# bunai3.net
KiCad netlist of a schematic drawn in EAGLE
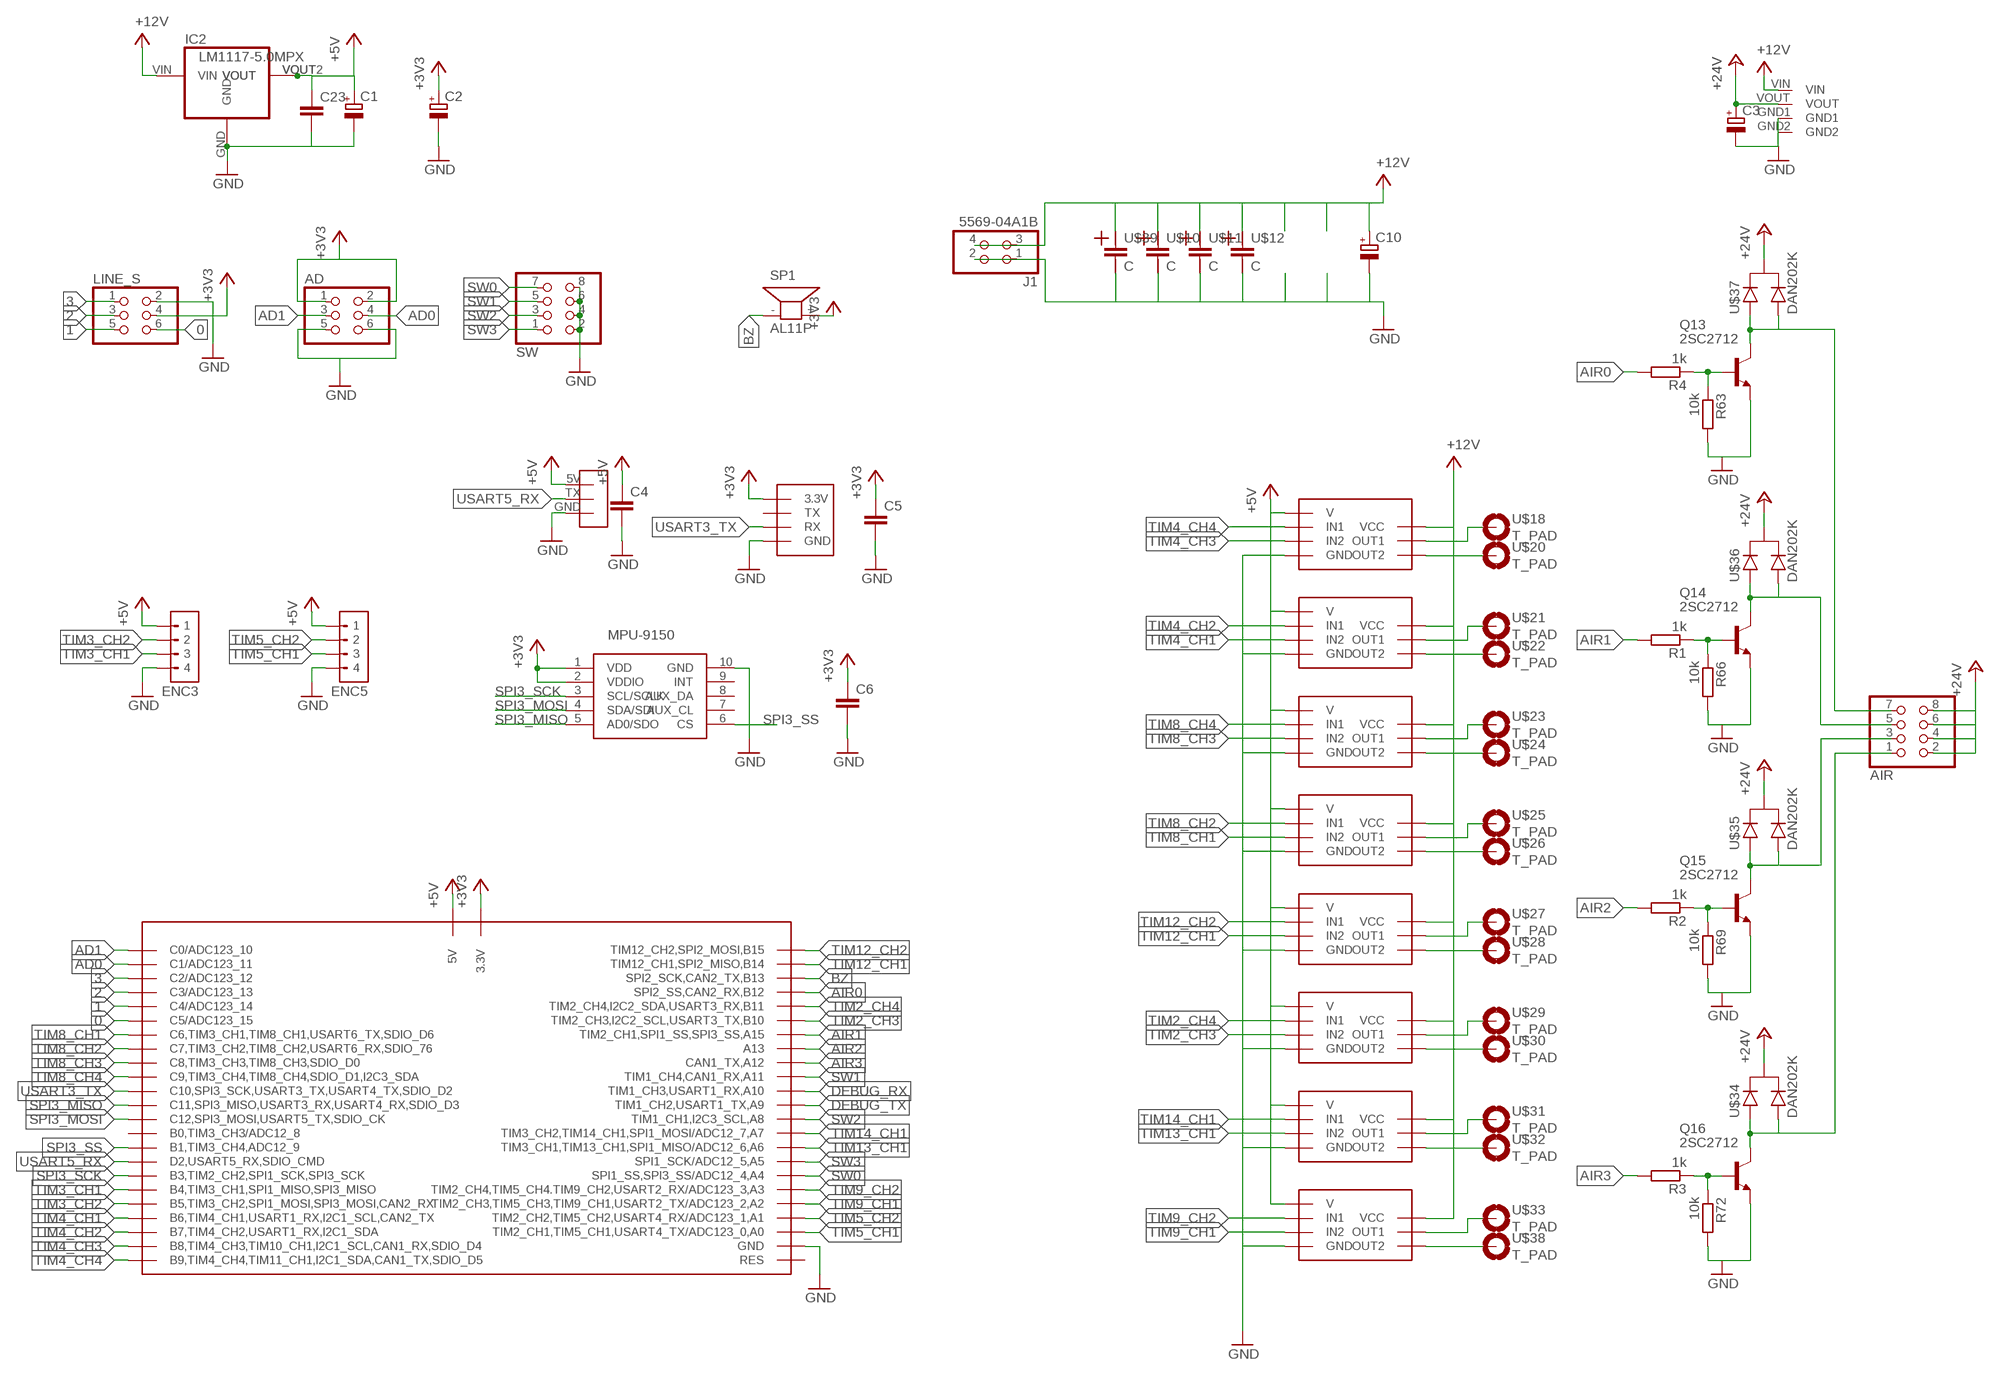
[diagram p0: schematic, sheet 1]

(export (version "E")
  (design (tool "Eeschema 10.0.6"))
  (components
    (comp (ref "AD")
      (value "PINHD-2X3/90")
      (footprint "eagle-import:2X03_90")
      (libsource (lib "eagle-import") (part "PINHD-2X3/90"))
    )
    (comp (ref "AIR")
      (value "PINHD-2X4/90")
      (footprint "eagle-import:2X04_90")
      (libsource (lib "eagle-import") (part "PINHD-2X4/90"))
    )
    (comp (ref "C1")
      (value "CPOL-EUE2.5-6")
      (footprint "eagle-import:E2,5-6")
      (libsource (lib "eagle-import") (part "CPOL-EUE2.5-6"))
    )
    (comp (ref "C2")
      (value "CPOL-EUE2.5-6")
      (footprint "eagle-import:E2,5-6")
      (libsource (lib "eagle-import") (part "CPOL-EUE2.5-6"))
    )
    (comp (ref "C3")
      (value "CPOL-EUE2.5-6")
      (footprint "eagle-import:E2,5-6")
      (libsource (lib "eagle-import") (part "CPOL-EUE2.5-6"))
    )
    (comp (ref "C4")
      (value "C-EU025-024X044")
      (footprint "eagle-import:C025-024X044")
      (libsource (lib "eagle-import") (part "C-EU025-024X044"))
    )
    (comp (ref "C5")
      (value "C-EU025-024X044")
      (footprint "eagle-import:C025-024X044")
      (libsource (lib "eagle-import") (part "C-EU025-024X044"))
    )
    (comp (ref "C6")
      (value "C-EU025-024X044")
      (footprint "eagle-import:C025-024X044")
      (libsource (lib "eagle-import") (part "C-EU025-024X044"))
    )
    (comp (ref "C10")
      (value "CPOL-EUE2.5-6")
      (footprint "eagle-import:E2,5-6")
      (libsource (lib "eagle-import") (part "CPOL-EUE2.5-6"))
    )
    (comp (ref "C23")
      (value "C-EUC0603K")
      (footprint "eagle-import:C0603K")
      (libsource (lib "eagle-import") (part "resistor_C-EUC0603K"))
    )
    (comp (ref "ENC3")
      (value "CN4-JST-XH-TOP")
      (footprint "eagle-import:JST-B4B-XH-A")
      (libsource (lib "eagle-import") (part "CN4-JST-XH-TOP"))
    )
    (comp (ref "ENC5")
      (value "CN4-JST-XH-TOP")
      (footprint "eagle-import:JST-B4B-XH-A")
      (libsource (lib "eagle-import") (part "CN4-JST-XH-TOP"))
    )
    (comp (ref "IC2")
      (value "LM1117-5.0MPX")
      (footprint "eagle-import:SOT223")
      (libsource (lib "eagle-import") (part "LM1117IMP-5.0"))
    )
    (comp (ref "J1")
      (value "5569-04A1B")
      (footprint "eagle-import:5569-04A1_2")
      (libsource (lib "eagle-import") (part "5569-04A1B"))
    )
    (comp (ref "LINE_S")
      (value "PINHD-2X3/90")
      (footprint "eagle-import:2X03_90")
      (libsource (lib "eagle-import") (part "PINHD-2X3/90"))
    )
    (comp (ref "MPU-9250")
      (value "MPU-9250")
      (footprint "eagle-import:MPU-9250")
      (libsource (lib "eagle-import") (part "MPU-9250"))
    )
    (comp (ref "Q13")
      (value "2SC2712")
      (footprint "eagle-import:SC-59(TYPE1)")
      (libsource (lib "eagle-import") (part "2SC2712"))
    )
    (comp (ref "Q14")
      (value "2SC2712")
      (footprint "eagle-import:SC-59(TYPE1)")
      (libsource (lib "eagle-import") (part "2SC2712"))
    )
    (comp (ref "Q15")
      (value "2SC2712")
      (footprint "eagle-import:SC-59(TYPE1)")
      (libsource (lib "eagle-import") (part "2SC2712"))
    )
    (comp (ref "Q16")
      (value "2SC2712")
      (footprint "eagle-import:SC-59(TYPE1)")
      (libsource (lib "eagle-import") (part "2SC2712"))
    )
    (comp (ref "R1")
      (value "1k")
      (footprint "eagle-import:0207_7")
      (libsource (lib "eagle-import") (part "R-EU_0207/7"))
    )
    (comp (ref "R2")
      (value "1k")
      (footprint "eagle-import:0207_7")
      (libsource (lib "eagle-import") (part "R-EU_0207/7"))
    )
    (comp (ref "R3")
      (value "1k")
      (footprint "eagle-import:0207_7")
      (libsource (lib "eagle-import") (part "R-EU_0207/7"))
    )
    (comp (ref "R4")
      (value "1k")
      (footprint "eagle-import:0207_7")
      (libsource (lib "eagle-import") (part "R-EU_0207/7"))
    )
    (comp (ref "R63")
      (value "10k")
      (footprint "eagle-import:R0603")
      (libsource (lib "eagle-import") (part "R-EU_R0603"))
    )
    (comp (ref "R66")
      (value "10k")
      (footprint "eagle-import:R0603")
      (libsource (lib "eagle-import") (part "R-EU_R0603"))
    )
    (comp (ref "R69")
      (value "10k")
      (footprint "eagle-import:R0603")
      (libsource (lib "eagle-import") (part "R-EU_R0603"))
    )
    (comp (ref "R72")
      (value "10k")
      (footprint "eagle-import:R0603")
      (libsource (lib "eagle-import") (part "R-EU_R0603"))
    )
    (comp (ref "SP1")
      (value "AL11P")
      (footprint "eagle-import:AL11P")
      (libsource (lib "eagle-import") (part "AL11P"))
    )
    (comp (ref "SW")
      (value "PINHD-2X4/90")
      (footprint "eagle-import:2X04_90")
      (libsource (lib "eagle-import") (part "PINHD-2X4/90"))
    )
    (comp (ref "U$1")
      (value "F4_T")
      (footprint "eagle-import:F4_T")
      (libsource (lib "eagle-import") (part "F4_T"))
    )
    (comp (ref "U$2")
      (value "BTM7752_T")
      (footprint "eagle-import:BTM7752_T")
      (libsource (lib "eagle-import") (part "BTM7752_T"))
    )
    (comp (ref "U$3")
      (value "BTM7752_T")
      (footprint "eagle-import:BTM7752_T")
      (libsource (lib "eagle-import") (part "BTM7752_T"))
    )
    (comp (ref "U$4")
      (value "BTM7752_T")
      (footprint "eagle-import:BTM7752_T")
      (libsource (lib "eagle-import") (part "BTM7752_T"))
    )
    (comp (ref "U$5")
      (value "BTM7752_T")
      (footprint "eagle-import:BTM7752_T")
      (libsource (lib "eagle-import") (part "BTM7752_T"))
    )
    (comp (ref "U$6")
      (value "BTM7752_T")
      (footprint "eagle-import:BTM7752_T")
      (libsource (lib "eagle-import") (part "BTM7752_T"))
    )
    (comp (ref "U$7")
      (value "BTM7752_T")
      (footprint "eagle-import:BTM7752_T")
      (libsource (lib "eagle-import") (part "BTM7752_T"))
    )
    (comp (ref "U$8")
      (value "BTM7752_T")
      (footprint "eagle-import:BTM7752_T")
      (libsource (lib "eagle-import") (part "BTM7752_T"))
    )
    (comp (ref "U$9")
      (value "BTM7752_T")
      (footprint "eagle-import:BTM7752_T")
      (libsource (lib "eagle-import") (part "BTM7752_T"))
    )
    (comp (ref "U$10") (value "C") (footprint "eagle-import:C") (libsource (lib "eagle-import") (part "C")))
    (comp (ref "U$11") (value "C") (footprint "eagle-import:C") (libsource (lib "eagle-import") (part "C")))
    (comp (ref "U$12") (value "C") (footprint "eagle-import:C") (libsource (lib "eagle-import") (part "C")))
    (comp (ref "U$16")
      (value "LT3580")
      (footprint "eagle-import:LT3580")
      (libsource (lib "eagle-import") (part "LT3580"))
    )
    (comp (ref "U$17")
      (value "SBDBT_5V")
      (footprint "eagle-import:SBDBT_5V")
      (libsource (lib "eagle-import") (part "SBDBT_5V"))
    )
    (comp (ref "U$18")
      (value "T_PAD")
      (footprint "eagle-import:T_PAD")
      (libsource (lib "eagle-import") (part "T_PAD"))
    )
    (comp (ref "U$19")
      (value "XBEE_T")
      (footprint "eagle-import:XBEE_T")
      (libsource (lib "eagle-import") (part "XBEE_T"))
    )
    (comp (ref "U$20")
      (value "T_PAD")
      (footprint "eagle-import:T_PAD")
      (libsource (lib "eagle-import") (part "T_PAD"))
    )
    (comp (ref "U$21")
      (value "T_PAD")
      (footprint "eagle-import:T_PAD")
      (libsource (lib "eagle-import") (part "T_PAD"))
    )
    (comp (ref "U$22")
      (value "T_PAD")
      (footprint "eagle-import:T_PAD")
      (libsource (lib "eagle-import") (part "T_PAD"))
    )
    (comp (ref "U$23")
      (value "T_PAD")
      (footprint "eagle-import:T_PAD")
      (libsource (lib "eagle-import") (part "T_PAD"))
    )
    (comp (ref "U$24")
      (value "T_PAD")
      (footprint "eagle-import:T_PAD")
      (libsource (lib "eagle-import") (part "T_PAD"))
    )
    (comp (ref "U$25")
      (value "T_PAD")
      (footprint "eagle-import:T_PAD")
      (libsource (lib "eagle-import") (part "T_PAD"))
    )
    (comp (ref "U$26")
      (value "T_PAD")
      (footprint "eagle-import:T_PAD")
      (libsource (lib "eagle-import") (part "T_PAD"))
    )
    (comp (ref "U$27")
      (value "T_PAD")
      (footprint "eagle-import:T_PAD")
      (libsource (lib "eagle-import") (part "T_PAD"))
    )
    (comp (ref "U$28")
      (value "T_PAD")
      (footprint "eagle-import:T_PAD")
      (libsource (lib "eagle-import") (part "T_PAD"))
    )
    (comp (ref "U$29")
      (value "T_PAD")
      (footprint "eagle-import:T_PAD")
      (libsource (lib "eagle-import") (part "T_PAD"))
    )
    (comp (ref "U$30")
      (value "T_PAD")
      (footprint "eagle-import:T_PAD")
      (libsource (lib "eagle-import") (part "T_PAD"))
    )
    (comp (ref "U$31")
      (value "T_PAD")
      (footprint "eagle-import:T_PAD")
      (libsource (lib "eagle-import") (part "T_PAD"))
    )
    (comp (ref "U$32")
      (value "T_PAD")
      (footprint "eagle-import:T_PAD")
      (libsource (lib "eagle-import") (part "T_PAD"))
    )
    (comp (ref "U$33")
      (value "T_PAD")
      (footprint "eagle-import:T_PAD")
      (libsource (lib "eagle-import") (part "T_PAD"))
    )
    (comp (ref "U$34")
      (value "DAN202K")
      (footprint "eagle-import:SC-59")
      (libsource (lib "eagle-import") (part "DAN202K"))
    )
    (comp (ref "U$35")
      (value "DAN202K")
      (footprint "eagle-import:SC-59")
      (libsource (lib "eagle-import") (part "DAN202K"))
    )
    (comp (ref "U$36")
      (value "DAN202K")
      (footprint "eagle-import:SC-59")
      (libsource (lib "eagle-import") (part "DAN202K"))
    )
    (comp (ref "U$37")
      (value "DAN202K")
      (footprint "eagle-import:SC-59")
      (libsource (lib "eagle-import") (part "DAN202K"))
    )
    (comp (ref "U$38")
      (value "T_PAD")
      (footprint "eagle-import:T_PAD")
      (libsource (lib "eagle-import") (part "T_PAD"))
    )
    (comp (ref "U$39") (value "C") (footprint "eagle-import:C") (libsource (lib "eagle-import") (part "C")))
  )
  (nets
    (net (code "1") (name "+3V3") (class "Default")
      (node (ref "AD") (pin "1") (pinfunction "1_1") (pintype "passive"))
      (node (ref "AD") (pin "2") (pinfunction "2_2") (pintype "passive"))
      (node (ref "C2") (pin "+") (pinfunction "+_+") (pintype "passive"))
      (node (ref "C5") (pin "1") (pinfunction "1_1") (pintype "passive"))
      (node (ref "C6") (pin "1") (pinfunction "1_1") (pintype "passive"))
      (node (ref "LINE_S") (pin "4") (pinfunction "4_4") (pintype "passive"))
      (node (ref "MPU-9250") (pin "1") (pinfunction "VDD_1") (pintype "bidirectional"))
      (node (ref "MPU-9250") (pin "2") (pinfunction "VDDIO_2") (pintype "bidirectional"))
      (node (ref "SP1") (pin "+") (pinfunction "2_+") (pintype "passive"))
      (node (ref "U$1") (pin "3.3V") (pinfunction "3.3V_3.3V") (pintype "bidirectional"))
      (node (ref "U$1") (pin "3.3V1") (pinfunction "3.3V_3.3V1") (pintype "bidirectional"))
      (node (ref "U$19") (pin "3.3V") (pinfunction "3.3V_3.3V") (pintype "bidirectional"))
    )
    (net (code "2") (name "+5V") (class "Default")
      (node (ref "C1") (pin "+") (pinfunction "+_+") (pintype "passive"))
      (node (ref "C23") (pin "1") (pinfunction "1_1") (pintype "passive"))
      (node (ref "C4") (pin "1") (pinfunction "1_1") (pintype "passive"))
      (node (ref "ENC3") (pin "1") (pinfunction "1_1") (pintype "passive"))
      (node (ref "ENC5") (pin "1") (pinfunction "1_1") (pintype "passive"))
      (node (ref "IC2") (pin "VOUT") (pinfunction "VOUT_VOUT") (pintype "output"))
      (node (ref "IC2") (pin "VOUT2") (pinfunction "VOUT_VOUT2") (pintype "output"))
      (node (ref "U$1") (pin "5V") (pinfunction "5V_5V") (pintype "bidirectional"))
      (node (ref "U$1") (pin "5V1") (pinfunction "5V_5V1") (pintype "bidirectional"))
      (node (ref "U$17") (pin "5V") (pinfunction "5V_5V") (pintype "bidirectional"))
      (node (ref "U$2") (pin "V") (pinfunction "V_V") (pintype "bidirectional"))
      (node (ref "U$3") (pin "V") (pinfunction "V_V") (pintype "bidirectional"))
      (node (ref "U$4") (pin "V") (pinfunction "V_V") (pintype "bidirectional"))
      (node (ref "U$5") (pin "V") (pinfunction "V_V") (pintype "bidirectional"))
      (node (ref "U$6") (pin "V") (pinfunction "V_V") (pintype "bidirectional"))
      (node (ref "U$7") (pin "V") (pinfunction "V_V") (pintype "bidirectional"))
      (node (ref "U$8") (pin "V") (pinfunction "V_V") (pintype "bidirectional"))
      (node (ref "U$9") (pin "V") (pinfunction "V_V") (pintype "bidirectional"))
    )
    (net (code "3") (name "+12V") (class "Default")
      (node (ref "C10") (pin "+") (pinfunction "+_+") (pintype "passive"))
      (node (ref "IC2") (pin "VIN") (pinfunction "VIN_VIN") (pintype "input"))
      (node (ref "J1") (pin "3") (pinfunction "3_3") (pintype "passive"))
      (node (ref "J1") (pin "4") (pinfunction "4_4") (pintype "passive"))
      (node (ref "U$16") (pin "VIN") (pinfunction "VIN_VIN") (pintype "bidirectional"))
      (node (ref "U$2") (pin "VCC1") (pinfunction "VCC_VCC1") (pintype "bidirectional"))
      (node (ref "U$2") (pin "VCC2") (pinfunction "VCC_VCC2") (pintype "bidirectional"))
      (node (ref "U$2") (pin "VCC3") (pinfunction "VCC_VCC3") (pintype "bidirectional"))
      (node (ref "U$2") (pin "VCC4") (pinfunction "VCC_VCC4") (pintype "bidirectional"))
      (node (ref "U$3") (pin "VCC1") (pinfunction "VCC_VCC1") (pintype "bidirectional"))
      (node (ref "U$3") (pin "VCC2") (pinfunction "VCC_VCC2") (pintype "bidirectional"))
      (node (ref "U$3") (pin "VCC3") (pinfunction "VCC_VCC3") (pintype "bidirectional"))
      (node (ref "U$3") (pin "VCC4") (pinfunction "VCC_VCC4") (pintype "bidirectional"))
      (node (ref "U$4") (pin "VCC1") (pinfunction "VCC_VCC1") (pintype "bidirectional"))
      (node (ref "U$4") (pin "VCC2") (pinfunction "VCC_VCC2") (pintype "bidirectional"))
      (node (ref "U$4") (pin "VCC3") (pinfunction "VCC_VCC3") (pintype "bidirectional"))
      (node (ref "U$4") (pin "VCC4") (pinfunction "VCC_VCC4") (pintype "bidirectional"))
      (node (ref "U$5") (pin "VCC1") (pinfunction "VCC_VCC1") (pintype "bidirectional"))
      (node (ref "U$5") (pin "VCC2") (pinfunction "VCC_VCC2") (pintype "bidirectional"))
      (node (ref "U$5") (pin "VCC3") (pinfunction "VCC_VCC3") (pintype "bidirectional"))
      (node (ref "U$5") (pin "VCC4") (pinfunction "VCC_VCC4") (pintype "bidirectional"))
      (node (ref "U$6") (pin "VCC1") (pinfunction "VCC_VCC1") (pintype "bidirectional"))
      (node (ref "U$6") (pin "VCC2") (pinfunction "VCC_VCC2") (pintype "bidirectional"))
      (node (ref "U$6") (pin "VCC3") (pinfunction "VCC_VCC3") (pintype "bidirectional"))
      (node (ref "U$6") (pin "VCC4") (pinfunction "VCC_VCC4") (pintype "bidirectional"))
      (node (ref "U$7") (pin "VCC1") (pinfunction "VCC_VCC1") (pintype "bidirectional"))
      (node (ref "U$7") (pin "VCC2") (pinfunction "VCC_VCC2") (pintype "bidirectional"))
      (node (ref "U$7") (pin "VCC3") (pinfunction "VCC_VCC3") (pintype "bidirectional"))
      (node (ref "U$7") (pin "VCC4") (pinfunction "VCC_VCC4") (pintype "bidirectional"))
      (node (ref "U$8") (pin "VCC1") (pinfunction "VCC_VCC1") (pintype "bidirectional"))
      (node (ref "U$8") (pin "VCC2") (pinfunction "VCC_VCC2") (pintype "bidirectional"))
      (node (ref "U$8") (pin "VCC3") (pinfunction "VCC_VCC3") (pintype "bidirectional"))
      (node (ref "U$8") (pin "VCC4") (pinfunction "VCC_VCC4") (pintype "bidirectional"))
      (node (ref "U$9") (pin "VCC1") (pinfunction "VCC_VCC1") (pintype "bidirectional"))
      (node (ref "U$9") (pin "VCC2") (pinfunction "VCC_VCC2") (pintype "bidirectional"))
      (node (ref "U$9") (pin "VCC3") (pinfunction "VCC_VCC3") (pintype "bidirectional"))
      (node (ref "U$9") (pin "VCC4") (pinfunction "VCC_VCC4") (pintype "bidirectional"))
    )
    (net (code "4") (name "+24V") (class "Default")
      (node (ref "AIR") (pin "2") (pinfunction "2_2") (pintype "passive"))
      (node (ref "AIR") (pin "4") (pinfunction "4_4") (pintype "passive"))
      (node (ref "AIR") (pin "6") (pinfunction "6_6") (pintype "passive"))
      (node (ref "AIR") (pin "8") (pinfunction "8_8") (pintype "passive"))
      (node (ref "C3") (pin "+") (pinfunction "+_+") (pintype "passive"))
      (node (ref "U$16") (pin "VOUT") (pinfunction "VOUT_VOUT") (pintype "bidirectional"))
      (node (ref "U$34") (pin "K") (pinfunction "K_K") (pintype "passive"))
      (node (ref "U$35") (pin "K") (pinfunction "K_K") (pintype "passive"))
      (node (ref "U$36") (pin "K") (pinfunction "K_K") (pintype "passive"))
      (node (ref "U$37") (pin "K") (pinfunction "K_K") (pintype "passive"))
    )
    (net (code "5") (name "0") (class "Default")
      (node (ref "LINE_S") (pin "6") (pinfunction "6_6") (pintype "passive"))
      (node (ref "U$1") (pin "C5") (pinfunction "C5/ADC123_15_C5") (pintype "bidirectional"))
    )
    (net (code "6") (name "1") (class "Default")
      (node (ref "LINE_S") (pin "5") (pinfunction "5_5") (pintype "passive"))
      (node (ref "U$1") (pin "C4") (pinfunction "C4/ADC123_14_C4") (pintype "bidirectional"))
    )
    (net (code "7") (name "2") (class "Default")
      (node (ref "LINE_S") (pin "3") (pinfunction "3_3") (pintype "passive"))
      (node (ref "U$1") (pin "C3") (pinfunction "C3/ADC123_13_C3") (pintype "bidirectional"))
    )
    (net (code "8") (name "3") (class "Default")
      (node (ref "LINE_S") (pin "1") (pinfunction "1_1") (pintype "passive"))
      (node (ref "U$1") (pin "C2") (pinfunction "C2/ADC123_12_C2") (pintype "bidirectional"))
    )
    (net (code "9") (name "AD0") (class "Default")
      (node (ref "AD") (pin "4") (pinfunction "4_4") (pintype "passive"))
      (node (ref "U$1") (pin "C1") (pinfunction "C1/ADC123_11_C1") (pintype "bidirectional"))
    )
    (net (code "10") (name "AD1") (class "Default")
      (node (ref "AD") (pin "3") (pinfunction "3_3") (pintype "passive"))
      (node (ref "U$1") (pin "C0") (pinfunction "C0/ADC123_10_C0") (pintype "bidirectional"))
    )
    (net (code "11") (name "AIR0") (class "Default")
      (node (ref "R4") (pin "2") (pinfunction "2_2") (pintype "passive"))
      (node (ref "U$1") (pin "B12") (pinfunction "SPI2_SS,CAN2_RX,B12_B12") (pintype "bidirectional"))
    )
    (net (code "12") (name "AIR1") (class "Default")
      (node (ref "R1") (pin "2") (pinfunction "2_2") (pintype "passive"))
      (node (ref "U$1") (pin "A15") (pinfunction "TIM2_CH1,SPI1_SS,SPI3_SS,A15_A15") (pintype "bidirectional"))
    )
    (net (code "13") (name "AIR2") (class "Default")
      (node (ref "R2") (pin "2") (pinfunction "2_2") (pintype "passive"))
      (node (ref "U$1") (pin "A13") (pinfunction "A13_A13") (pintype "bidirectional"))
    )
    (net (code "14") (name "AIR3") (class "Default")
      (node (ref "R3") (pin "2") (pinfunction "2_2") (pintype "passive"))
      (node (ref "U$1") (pin "A12") (pinfunction "CAN1_TX,A12_A12") (pintype "bidirectional"))
    )
    (net (code "15") (name "BZ") (class "Default")
      (node (ref "SP1") (pin "-") (pinfunction "1_-") (pintype "passive"))
      (node (ref "U$1") (pin "B13") (pinfunction "SPI2_SCK,CAN2_TX,B13_B13") (pintype "bidirectional"))
    )
    (net (code "16") (name "DEBUG_RX") (class "Default")
      (node (ref "U$1") (pin "A10") (pinfunction "TIM1_CH3,USART1_RX,A10_A10") (pintype "bidirectional"))
    )
    (net (code "17") (name "DEBUG_TX") (class "Default")
      (node (ref "U$1") (pin "A9") (pinfunction "TIM1_CH2,USART1_TX,A9_A9") (pintype "bidirectional"))
    )
    (net (code "18") (name "GND") (class "Default")
      (node (ref "AD") (pin "5") (pinfunction "5_5") (pintype "passive"))
      (node (ref "AD") (pin "6") (pinfunction "6_6") (pintype "passive"))
      (node (ref "C1") (pin "-") (pinfunction "-_-") (pintype "passive"))
      (node (ref "C10") (pin "-") (pinfunction "-_-") (pintype "passive"))
      (node (ref "C2") (pin "-") (pinfunction "-_-") (pintype "passive"))
      (node (ref "C23") (pin "2") (pinfunction "2_2") (pintype "passive"))
      (node (ref "C3") (pin "-") (pinfunction "-_-") (pintype "passive"))
      (node (ref "C4") (pin "2") (pinfunction "2_2") (pintype "passive"))
      (node (ref "C5") (pin "2") (pinfunction "2_2") (pintype "passive"))
      (node (ref "C6") (pin "2") (pinfunction "2_2") (pintype "passive"))
      (node (ref "ENC3") (pin "4") (pinfunction "4_4") (pintype "passive"))
      (node (ref "ENC5") (pin "4") (pinfunction "4_4") (pintype "passive"))
      (node (ref "IC2") (pin "GND") (pinfunction "GND_GND") (pintype "power_in"))
      (node (ref "J1") (pin "1") (pinfunction "1_1") (pintype "passive"))
      (node (ref "J1") (pin "2") (pinfunction "2_2") (pintype "passive"))
      (node (ref "LINE_S") (pin "2") (pinfunction "2_2") (pintype "passive"))
      (node (ref "MPU-9250") (pin "10") (pinfunction "GND_10") (pintype "bidirectional"))
      (node (ref "Q13") (pin "E") (pinfunction "E_E") (pintype "passive"))
      (node (ref "Q14") (pin "E") (pinfunction "E_E") (pintype "passive"))
      (node (ref "Q15") (pin "E") (pinfunction "E_E") (pintype "passive"))
      (node (ref "Q16") (pin "E") (pinfunction "E_E") (pintype "passive"))
      (node (ref "R63") (pin "2") (pinfunction "2_2") (pintype "passive"))
      (node (ref "R66") (pin "2") (pinfunction "2_2") (pintype "passive"))
      (node (ref "R69") (pin "2") (pinfunction "2_2") (pintype "passive"))
      (node (ref "R72") (pin "2") (pinfunction "2_2") (pintype "passive"))
      (node (ref "SW") (pin "2") (pinfunction "2_2") (pintype "passive"))
      (node (ref "SW") (pin "4") (pinfunction "4_4") (pintype "passive"))
      (node (ref "SW") (pin "6") (pinfunction "6_6") (pintype "passive"))
      (node (ref "SW") (pin "8") (pinfunction "8_8") (pintype "passive"))
      (node (ref "U$1") (pin "GND1") (pinfunction "GND_GND1") (pintype "bidirectional"))
      (node (ref "U$1") (pin "GND2") (pinfunction "GND_GND2") (pintype "bidirectional"))
      (node (ref "U$1") (pin "GND3") (pinfunction "GND_GND3") (pintype "bidirectional"))
      (node (ref "U$16") (pin "GND1") (pinfunction "GND1_GND1") (pintype "bidirectional"))
      (node (ref "U$16") (pin "GND2") (pinfunction "GND2_GND2") (pintype "bidirectional"))
      (node (ref "U$17") (pin "GND") (pinfunction "GND_GND") (pintype "bidirectional"))
      (node (ref "U$19") (pin "GND") (pinfunction "GND_GND") (pintype "bidirectional"))
      (node (ref "U$2") (pin "GND1") (pinfunction "GND_GND1") (pintype "bidirectional"))
      (node (ref "U$2") (pin "GND2") (pinfunction "GND_GND2") (pintype "bidirectional"))
      (node (ref "U$2") (pin "GND3") (pinfunction "GND_GND3") (pintype "bidirectional"))
      (node (ref "U$3") (pin "GND1") (pinfunction "GND_GND1") (pintype "bidirectional"))
      (node (ref "U$3") (pin "GND2") (pinfunction "GND_GND2") (pintype "bidirectional"))
      (node (ref "U$3") (pin "GND3") (pinfunction "GND_GND3") (pintype "bidirectional"))
      (node (ref "U$4") (pin "GND1") (pinfunction "GND_GND1") (pintype "bidirectional"))
      (node (ref "U$4") (pin "GND2") (pinfunction "GND_GND2") (pintype "bidirectional"))
      (node (ref "U$4") (pin "GND3") (pinfunction "GND_GND3") (pintype "bidirectional"))
      (node (ref "U$5") (pin "GND1") (pinfunction "GND_GND1") (pintype "bidirectional"))
      (node (ref "U$5") (pin "GND2") (pinfunction "GND_GND2") (pintype "bidirectional"))
      (node (ref "U$5") (pin "GND3") (pinfunction "GND_GND3") (pintype "bidirectional"))
      (node (ref "U$6") (pin "GND1") (pinfunction "GND_GND1") (pintype "bidirectional"))
      (node (ref "U$6") (pin "GND2") (pinfunction "GND_GND2") (pintype "bidirectional"))
      (node (ref "U$6") (pin "GND3") (pinfunction "GND_GND3") (pintype "bidirectional"))
      (node (ref "U$7") (pin "GND1") (pinfunction "GND_GND1") (pintype "bidirectional"))
      (node (ref "U$7") (pin "GND2") (pinfunction "GND_GND2") (pintype "bidirectional"))
      (node (ref "U$7") (pin "GND3") (pinfunction "GND_GND3") (pintype "bidirectional"))
      (node (ref "U$8") (pin "GND1") (pinfunction "GND_GND1") (pintype "bidirectional"))
      (node (ref "U$8") (pin "GND2") (pinfunction "GND_GND2") (pintype "bidirectional"))
      (node (ref "U$8") (pin "GND3") (pinfunction "GND_GND3") (pintype "bidirectional"))
      (node (ref "U$9") (pin "GND1") (pinfunction "GND_GND1") (pintype "bidirectional"))
      (node (ref "U$9") (pin "GND2") (pinfunction "GND_GND2") (pintype "bidirectional"))
      (node (ref "U$9") (pin "GND3") (pinfunction "GND_GND3") (pintype "bidirectional"))
    )
    (net (code "19") (name "Net-(Q13-PadB)") (class "Default")
      (node (ref "Q13") (pin "B") (pinfunction "B_B") (pintype "passive"))
      (node (ref "R4") (pin "1") (pinfunction "1_1") (pintype "passive"))
      (node (ref "R63") (pin "1") (pinfunction "1_1") (pintype "passive"))
    )
    (net (code "20") (name "Net-(Q14-PadB)") (class "Default")
      (node (ref "Q14") (pin "B") (pinfunction "B_B") (pintype "passive"))
      (node (ref "R1") (pin "1") (pinfunction "1_1") (pintype "passive"))
      (node (ref "R66") (pin "1") (pinfunction "1_1") (pintype "passive"))
    )
    (net (code "21") (name "Net-(Q15-PadB)") (class "Default")
      (node (ref "Q15") (pin "B") (pinfunction "B_B") (pintype "passive"))
      (node (ref "R2") (pin "1") (pinfunction "1_1") (pintype "passive"))
      (node (ref "R69") (pin "1") (pinfunction "1_1") (pintype "passive"))
    )
    (net (code "22") (name "Net-(Q16-PadB)") (class "Default")
      (node (ref "Q16") (pin "B") (pinfunction "B_B") (pintype "passive"))
      (node (ref "R3") (pin "1") (pinfunction "1_1") (pintype "passive"))
      (node (ref "R72") (pin "1") (pinfunction "1_1") (pintype "passive"))
    )
    (net (code "23") (name "Net-(U$18-MOUNT)") (class "Default")
      (node (ref "U$18") (pin "P$1") (pinfunction "MOUNT_P$1") (pintype "passive"))
      (node (ref "U$9") (pin "OUT11") (pinfunction "OUT1_OUT11") (pintype "bidirectional"))
      (node (ref "U$9") (pin "OUT12") (pinfunction "OUT1_OUT12") (pintype "bidirectional"))
      (node (ref "U$9") (pin "OUT13") (pinfunction "OUT1_OUT13") (pintype "bidirectional"))
      (node (ref "U$9") (pin "OUT14") (pinfunction "OUT1_OUT14") (pintype "bidirectional"))
    )
    (net (code "24") (name "Net-(U$20-MOUNT)") (class "Default")
      (node (ref "U$20") (pin "P$1") (pinfunction "MOUNT_P$1") (pintype "passive"))
      (node (ref "U$9") (pin "OUT21") (pinfunction "OUT2_OUT21") (pintype "bidirectional"))
      (node (ref "U$9") (pin "OUT22") (pinfunction "OUT2_OUT22") (pintype "bidirectional"))
      (node (ref "U$9") (pin "OUT23") (pinfunction "OUT2_OUT23") (pintype "bidirectional"))
      (node (ref "U$9") (pin "OUT24") (pinfunction "OUT2_OUT24") (pintype "bidirectional"))
    )
    (net (code "25") (name "Net-(U$21-MOUNT)") (class "Default")
      (node (ref "U$21") (pin "P$1") (pinfunction "MOUNT_P$1") (pintype "passive"))
      (node (ref "U$8") (pin "OUT11") (pinfunction "OUT1_OUT11") (pintype "bidirectional"))
      (node (ref "U$8") (pin "OUT12") (pinfunction "OUT1_OUT12") (pintype "bidirectional"))
      (node (ref "U$8") (pin "OUT13") (pinfunction "OUT1_OUT13") (pintype "bidirectional"))
      (node (ref "U$8") (pin "OUT14") (pinfunction "OUT1_OUT14") (pintype "bidirectional"))
    )
    (net (code "26") (name "Net-(U$22-MOUNT)") (class "Default")
      (node (ref "U$22") (pin "P$1") (pinfunction "MOUNT_P$1") (pintype "passive"))
      (node (ref "U$8") (pin "OUT21") (pinfunction "OUT2_OUT21") (pintype "bidirectional"))
      (node (ref "U$8") (pin "OUT22") (pinfunction "OUT2_OUT22") (pintype "bidirectional"))
      (node (ref "U$8") (pin "OUT23") (pinfunction "OUT2_OUT23") (pintype "bidirectional"))
      (node (ref "U$8") (pin "OUT24") (pinfunction "OUT2_OUT24") (pintype "bidirectional"))
    )
    (net (code "27") (name "Net-(U$23-MOUNT)") (class "Default")
      (node (ref "U$23") (pin "P$1") (pinfunction "MOUNT_P$1") (pintype "passive"))
      (node (ref "U$7") (pin "OUT11") (pinfunction "OUT1_OUT11") (pintype "bidirectional"))
      (node (ref "U$7") (pin "OUT12") (pinfunction "OUT1_OUT12") (pintype "bidirectional"))
      (node (ref "U$7") (pin "OUT13") (pinfunction "OUT1_OUT13") (pintype "bidirectional"))
      (node (ref "U$7") (pin "OUT14") (pinfunction "OUT1_OUT14") (pintype "bidirectional"))
    )
    (net (code "28") (name "Net-(U$24-MOUNT)") (class "Default")
      (node (ref "U$24") (pin "P$1") (pinfunction "MOUNT_P$1") (pintype "passive"))
      (node (ref "U$7") (pin "OUT21") (pinfunction "OUT2_OUT21") (pintype "bidirectional"))
      (node (ref "U$7") (pin "OUT22") (pinfunction "OUT2_OUT22") (pintype "bidirectional"))
      (node (ref "U$7") (pin "OUT23") (pinfunction "OUT2_OUT23") (pintype "bidirectional"))
      (node (ref "U$7") (pin "OUT24") (pinfunction "OUT2_OUT24") (pintype "bidirectional"))
    )
    (net (code "29") (name "Net-(U$25-MOUNT)") (class "Default")
      (node (ref "U$25") (pin "P$1") (pinfunction "MOUNT_P$1") (pintype "passive"))
      (node (ref "U$6") (pin "OUT11") (pinfunction "OUT1_OUT11") (pintype "bidirectional"))
      (node (ref "U$6") (pin "OUT12") (pinfunction "OUT1_OUT12") (pintype "bidirectional"))
      (node (ref "U$6") (pin "OUT13") (pinfunction "OUT1_OUT13") (pintype "bidirectional"))
      (node (ref "U$6") (pin "OUT14") (pinfunction "OUT1_OUT14") (pintype "bidirectional"))
    )
    (net (code "30") (name "Net-(U$26-MOUNT)") (class "Default")
      (node (ref "U$26") (pin "P$1") (pinfunction "MOUNT_P$1") (pintype "passive"))
      (node (ref "U$6") (pin "OUT21") (pinfunction "OUT2_OUT21") (pintype "bidirectional"))
      (node (ref "U$6") (pin "OUT22") (pinfunction "OUT2_OUT22") (pintype "bidirectional"))
      (node (ref "U$6") (pin "OUT23") (pinfunction "OUT2_OUT23") (pintype "bidirectional"))
      (node (ref "U$6") (pin "OUT24") (pinfunction "OUT2_OUT24") (pintype "bidirectional"))
    )
    (net (code "31") (name "Net-(U$27-MOUNT)") (class "Default")
      (node (ref "U$27") (pin "P$1") (pinfunction "MOUNT_P$1") (pintype "passive"))
      (node (ref "U$5") (pin "OUT11") (pinfunction "OUT1_OUT11") (pintype "bidirectional"))
      (node (ref "U$5") (pin "OUT12") (pinfunction "OUT1_OUT12") (pintype "bidirectional"))
      (node (ref "U$5") (pin "OUT13") (pinfunction "OUT1_OUT13") (pintype "bidirectional"))
      (node (ref "U$5") (pin "OUT14") (pinfunction "OUT1_OUT14") (pintype "bidirectional"))
    )
    (net (code "32") (name "Net-(U$28-MOUNT)") (class "Default")
      (node (ref "U$28") (pin "P$1") (pinfunction "MOUNT_P$1") (pintype "passive"))
      (node (ref "U$5") (pin "OUT21") (pinfunction "OUT2_OUT21") (pintype "bidirectional"))
      (node (ref "U$5") (pin "OUT22") (pinfunction "OUT2_OUT22") (pintype "bidirectional"))
      (node (ref "U$5") (pin "OUT23") (pinfunction "OUT2_OUT23") (pintype "bidirectional"))
      (node (ref "U$5") (pin "OUT24") (pinfunction "OUT2_OUT24") (pintype "bidirectional"))
    )
    (net (code "33") (name "Net-(U$29-MOUNT)") (class "Default")
      (node (ref "U$29") (pin "P$1") (pinfunction "MOUNT_P$1") (pintype "passive"))
      (node (ref "U$4") (pin "OUT11") (pinfunction "OUT1_OUT11") (pintype "bidirectional"))
      (node (ref "U$4") (pin "OUT12") (pinfunction "OUT1_OUT12") (pintype "bidirectional"))
      (node (ref "U$4") (pin "OUT13") (pinfunction "OUT1_OUT13") (pintype "bidirectional"))
      (node (ref "U$4") (pin "OUT14") (pinfunction "OUT1_OUT14") (pintype "bidirectional"))
    )
    (net (code "34") (name "Net-(U$30-MOUNT)") (class "Default")
      (node (ref "U$30") (pin "P$1") (pinfunction "MOUNT_P$1") (pintype "passive"))
      (node (ref "U$4") (pin "OUT21") (pinfunction "OUT2_OUT21") (pintype "bidirectional"))
      (node (ref "U$4") (pin "OUT22") (pinfunction "OUT2_OUT22") (pintype "bidirectional"))
      (node (ref "U$4") (pin "OUT23") (pinfunction "OUT2_OUT23") (pintype "bidirectional"))
      (node (ref "U$4") (pin "OUT24") (pinfunction "OUT2_OUT24") (pintype "bidirectional"))
    )
    (net (code "35") (name "Net-(U$31-MOUNT)") (class "Default")
      (node (ref "U$3") (pin "OUT11") (pinfunction "OUT1_OUT11") (pintype "bidirectional"))
      (node (ref "U$3") (pin "OUT12") (pinfunction "OUT1_OUT12") (pintype "bidirectional"))
      (node (ref "U$3") (pin "OUT13") (pinfunction "OUT1_OUT13") (pintype "bidirectional"))
      (node (ref "U$3") (pin "OUT14") (pinfunction "OUT1_OUT14") (pintype "bidirectional"))
      (node (ref "U$31") (pin "P$1") (pinfunction "MOUNT_P$1") (pintype "passive"))
    )
    (net (code "36") (name "Net-(U$32-MOUNT)") (class "Default")
      (node (ref "U$3") (pin "OUT21") (pinfunction "OUT2_OUT21") (pintype "bidirectional"))
      (node (ref "U$3") (pin "OUT22") (pinfunction "OUT2_OUT22") (pintype "bidirectional"))
      (node (ref "U$3") (pin "OUT23") (pinfunction "OUT2_OUT23") (pintype "bidirectional"))
      (node (ref "U$3") (pin "OUT24") (pinfunction "OUT2_OUT24") (pintype "bidirectional"))
      (node (ref "U$32") (pin "P$1") (pinfunction "MOUNT_P$1") (pintype "passive"))
    )
    (net (code "37") (name "Net-(U$33-MOUNT)") (class "Default")
      (node (ref "U$2") (pin "OUT11") (pinfunction "OUT1_OUT11") (pintype "bidirectional"))
      (node (ref "U$2") (pin "OUT12") (pinfunction "OUT1_OUT12") (pintype "bidirectional"))
      (node (ref "U$2") (pin "OUT13") (pinfunction "OUT1_OUT13") (pintype "bidirectional"))
      (node (ref "U$2") (pin "OUT14") (pinfunction "OUT1_OUT14") (pintype "bidirectional"))
      (node (ref "U$33") (pin "P$1") (pinfunction "MOUNT_P$1") (pintype "passive"))
    )
    (net (code "38") (name "Net-(U$34-A1)") (class "Default")
      (node (ref "AIR") (pin "1") (pinfunction "1_1") (pintype "passive"))
      (node (ref "Q16") (pin "C") (pinfunction "C_C") (pintype "passive"))
      (node (ref "U$34") (pin "A@1") (pinfunction "A1_A@1") (pintype "passive"))
      (node (ref "U$34") (pin "A@2") (pinfunction "A2_A@2") (pintype "passive"))
    )
    (net (code "39") (name "Net-(U$35-A1)") (class "Default")
      (node (ref "AIR") (pin "3") (pinfunction "3_3") (pintype "passive"))
      (node (ref "Q15") (pin "C") (pinfunction "C_C") (pintype "passive"))
      (node (ref "U$35") (pin "A@1") (pinfunction "A1_A@1") (pintype "passive"))
      (node (ref "U$35") (pin "A@2") (pinfunction "A2_A@2") (pintype "passive"))
    )
    (net (code "40") (name "Net-(U$36-A1)") (class "Default")
      (node (ref "AIR") (pin "5") (pinfunction "5_5") (pintype "passive"))
      (node (ref "Q14") (pin "C") (pinfunction "C_C") (pintype "passive"))
      (node (ref "U$36") (pin "A@1") (pinfunction "A1_A@1") (pintype "passive"))
      (node (ref "U$36") (pin "A@2") (pinfunction "A2_A@2") (pintype "passive"))
    )
    (net (code "41") (name "Net-(U$37-A1)") (class "Default")
      (node (ref "AIR") (pin "7") (pinfunction "7_7") (pintype "passive"))
      (node (ref "Q13") (pin "C") (pinfunction "C_C") (pintype "passive"))
      (node (ref "U$37") (pin "A@1") (pinfunction "A1_A@1") (pintype "passive"))
      (node (ref "U$37") (pin "A@2") (pinfunction "A2_A@2") (pintype "passive"))
    )
    (net (code "42") (name "Net-(U$38-MOUNT)") (class "Default")
      (node (ref "U$2") (pin "OUT21") (pinfunction "OUT2_OUT21") (pintype "bidirectional"))
      (node (ref "U$2") (pin "OUT22") (pinfunction "OUT2_OUT22") (pintype "bidirectional"))
      (node (ref "U$2") (pin "OUT23") (pinfunction "OUT2_OUT23") (pintype "bidirectional"))
      (node (ref "U$2") (pin "OUT24") (pinfunction "OUT2_OUT24") (pintype "bidirectional"))
      (node (ref "U$38") (pin "P$1") (pinfunction "MOUNT_P$1") (pintype "passive"))
    )
    (net (code "43") (name "SPI3_MISO") (class "Default")
      (node (ref "MPU-9250") (pin "5") (pinfunction "AD0/SDO_5") (pintype "bidirectional"))
      (node (ref "U$1") (pin "C11") (pinfunction "C11,SPI3_MISO,USART3_RX,USART4_RX,SDIO_D3_C11") (pintype "bidirectional"))
    )
    (net (code "44") (name "SPI3_MOSI") (class "Default")
      (node (ref "MPU-9250") (pin "4") (pinfunction "SDA/SDI_4") (pintype "bidirectional"))
      (node (ref "U$1") (pin "C12") (pinfunction "C12,SPI3_MOSI,USART5_TX,SDIO_CK_C12") (pintype "bidirectional"))
    )
    (net (code "45") (name "SPI3_SCK") (class "Default")
      (node (ref "MPU-9250") (pin "3") (pinfunction "SCL/SCLK_3") (pintype "bidirectional"))
      (node (ref "U$1") (pin "B3") (pinfunction "B3,TIM2_CH2,SPI1_SCK,SPI3_SCK_B3") (pintype "bidirectional"))
    )
    (net (code "46") (name "SPI3_SS") (class "Default")
      (node (ref "MPU-9250") (pin "6") (pinfunction "CS_6") (pintype "bidirectional"))
      (node (ref "U$1") (pin "B1") (pinfunction "B1,TIM3_CH4,ADC12_9_B1") (pintype "bidirectional"))
    )
    (net (code "47") (name "SW0") (class "Default")
      (node (ref "SW") (pin "7") (pinfunction "7_7") (pintype "passive"))
      (node (ref "U$1") (pin "A4") (pinfunction "SPI1_SS,SPI3_SS/ADC12_4,A4_A4") (pintype "bidirectional"))
    )
    (net (code "48") (name "SW1") (class "Default")
      (node (ref "SW") (pin "5") (pinfunction "5_5") (pintype "passive"))
      (node (ref "U$1") (pin "A11") (pinfunction "TIM1_CH4,CAN1_RX,A11_A11") (pintype "bidirectional"))
    )
    (net (code "49") (name "SW2") (class "Default")
      (node (ref "SW") (pin "3") (pinfunction "3_3") (pintype "passive"))
      (node (ref "U$1") (pin "A8") (pinfunction "TIM1_CH1,I2C3_SCL,A8_A8") (pintype "bidirectional"))
    )
    (net (code "50") (name "SW3") (class "Default")
      (node (ref "SW") (pin "1") (pinfunction "1_1") (pintype "passive"))
      (node (ref "U$1") (pin "A5") (pinfunction "SPI1_SCK/ADC12_5,A5_A5") (pintype "bidirectional"))
    )
    (net (code "51") (name "TIM2_CH3") (class "Default")
      (node (ref "U$1") (pin "B10") (pinfunction "TIM2_CH3,I2C2_SCL,USART3_TX,B10_B10") (pintype "bidirectional"))
      (node (ref "U$4") (pin "IN2") (pinfunction "IN2_IN2") (pintype "bidirectional"))
    )
    (net (code "52") (name "TIM2_CH4") (class "Default")
      (node (ref "U$1") (pin "B11") (pinfunction "TIM2_CH4,I2C2_SDA,USART3_RX,B11_B11") (pintype "bidirectional"))
      (node (ref "U$4") (pin "IN1") (pinfunction "IN1_IN1") (pintype "bidirectional"))
    )
    (net (code "53") (name "TIM3_CH1") (class "Default")
      (node (ref "ENC3") (pin "3") (pinfunction "3_3") (pintype "passive"))
      (node (ref "U$1") (pin "B4") (pinfunction "B4,TIM3_CH1,SPI1_MISO,SPI3_MISO_B4") (pintype "bidirectional"))
    )
    (net (code "54") (name "TIM3_CH2") (class "Default")
      (node (ref "ENC3") (pin "2") (pinfunction "2_2") (pintype "passive"))
      (node (ref "U$1") (pin "B5") (pinfunction "B5,TIM3_CH2,SPI1_MOSI,SPI3_MOSI,CAN2_RX_B5") (pintype "bidirectional"))
    )
    (net (code "55") (name "TIM4_CH1") (class "Default")
      (node (ref "U$1") (pin "B6") (pinfunction "B6,TIM4_CH1,USART1_RX,I2C1_SCL,CAN2_TX_B6") (pintype "bidirectional"))
      (node (ref "U$8") (pin "IN2") (pinfunction "IN2_IN2") (pintype "bidirectional"))
    )
    (net (code "56") (name "TIM4_CH2") (class "Default")
      (node (ref "U$1") (pin "B7") (pinfunction "B7,TIM4_CH2,USART1_RX,I2C1_SDA_B7") (pintype "bidirectional"))
      (node (ref "U$8") (pin "IN1") (pinfunction "IN1_IN1") (pintype "bidirectional"))
    )
    (net (code "57") (name "TIM4_CH3") (class "Default")
      (node (ref "U$1") (pin "B8") (pinfunction "B8,TIM4_CH3,TIM10_CH1,I2C1_SCL,CAN1_RX,SDIO_D4_B8") (pintype "bidirectional"))
      (node (ref "U$9") (pin "IN2") (pinfunction "IN2_IN2") (pintype "bidirectional"))
    )
    (net (code "58") (name "TIM4_CH4") (class "Default")
      (node (ref "U$1") (pin "B9") (pinfunction "B9,TIM4_CH4,TIM11_CH1,I2C1_SDA,CAN1_TX,SDIO_D5_B9") (pintype "bidirectional"))
      (node (ref "U$9") (pin "IN1") (pinfunction "IN1_IN1") (pintype "bidirectional"))
    )
    (net (code "59") (name "TIM5_CH1") (class "Default")
      (node (ref "ENC5") (pin "3") (pinfunction "3_3") (pintype "passive"))
      (node (ref "U$1") (pin "A0") (pinfunction "TIM2_CH1,TIM5_CH1,USART4_TX/ADC123_0,A0_A0") (pintype "bidirectional"))
    )
    (net (code "60") (name "TIM5_CH2") (class "Default")
      (node (ref "ENC5") (pin "2") (pinfunction "2_2") (pintype "passive"))
      (node (ref "U$1") (pin "A1") (pinfunction "TIM2_CH2,TIM5_CH2,USART4_RX/ADC123_1,A1_A1") (pintype "bidirectional"))
    )
    (net (code "61") (name "TIM8_CH1") (class "Default")
      (node (ref "U$1") (pin "C6") (pinfunction "C6,TIM3_CH1,TIM8_CH1,USART6_TX,SDIO_D6_C6") (pintype "bidirectional"))
      (node (ref "U$6") (pin "IN2") (pinfunction "IN2_IN2") (pintype "bidirectional"))
    )
    (net (code "62") (name "TIM8_CH2") (class "Default")
      (node (ref "U$1") (pin "C7") (pinfunction "C7,TIM3_CH2,TIM8_CH2,USART6_RX,SDIO_76_C7") (pintype "bidirectional"))
      (node (ref "U$6") (pin "IN1") (pinfunction "IN1_IN1") (pintype "bidirectional"))
    )
    (net (code "63") (name "TIM8_CH3") (class "Default")
      (node (ref "U$1") (pin "C8") (pinfunction "C8,TIM3_CH3,TIM8_CH3,SDIO_D0_C8") (pintype "bidirectional"))
      (node (ref "U$7") (pin "IN2") (pinfunction "IN2_IN2") (pintype "bidirectional"))
    )
    (net (code "64") (name "TIM8_CH4") (class "Default")
      (node (ref "U$1") (pin "C9") (pinfunction "C9,TIM3_CH4,TIM8_CH4,SDIO_D1,I2C3_SDA_C9") (pintype "bidirectional"))
      (node (ref "U$7") (pin "IN1") (pinfunction "IN1_IN1") (pintype "bidirectional"))
    )
    (net (code "65") (name "TIM9_CH1") (class "Default")
      (node (ref "U$1") (pin "A2") (pinfunction "TIM2_CH3,TIM5_CH3,TIM9_CH1,USART2_TX/ADC123_2,A2_A2") (pintype "bidirectional"))
      (node (ref "U$2") (pin "IN2") (pinfunction "IN2_IN2") (pintype "bidirectional"))
    )
    (net (code "66") (name "TIM9_CH2") (class "Default")
      (node (ref "U$1") (pin "A3") (pinfunction "TIM2_CH4,TIM5_CH4.TIM9_CH2,USART2_RX/ADC123_3,A3_A3") (pintype "bidirectional"))
      (node (ref "U$2") (pin "IN1") (pinfunction "IN1_IN1") (pintype "bidirectional"))
    )
    (net (code "67") (name "TIM12_CH1") (class "Default")
      (node (ref "U$1") (pin "B14") (pinfunction "TIM12_CH1,SPI2_MISO,B14_B14") (pintype "bidirectional"))
      (node (ref "U$5") (pin "IN2") (pinfunction "IN2_IN2") (pintype "bidirectional"))
    )
    (net (code "68") (name "TIM12_CH2") (class "Default")
      (node (ref "U$1") (pin "B15") (pinfunction "TIM12_CH2,SPI2_MOSI,B15_B15") (pintype "bidirectional"))
      (node (ref "U$5") (pin "IN1") (pinfunction "IN1_IN1") (pintype "bidirectional"))
    )
    (net (code "69") (name "TIM13_CH1") (class "Default")
      (node (ref "U$1") (pin "A6") (pinfunction "TIM3_CH1,TIM13_CH1,SPI1_MISO/ADC12_6,A6_A6") (pintype "bidirectional"))
      (node (ref "U$3") (pin "IN2") (pinfunction "IN2_IN2") (pintype "bidirectional"))
    )
    (net (code "70") (name "TIM14_CH1") (class "Default")
      (node (ref "U$1") (pin "A7") (pinfunction "TIM3_CH2,TIM14_CH1,SPI1_MOSI/ADC12_7,A7_A7") (pintype "bidirectional"))
      (node (ref "U$3") (pin "IN1") (pinfunction "IN1_IN1") (pintype "bidirectional"))
    )
    (net (code "71") (name "USART3_TX") (class "Default")
      (node (ref "U$1") (pin "C10") (pinfunction "C10,SPI3_SCK,USART3_TX,USART4_TX,SDIO_D2_C10") (pintype "bidirectional"))
      (node (ref "U$19") (pin "RX") (pinfunction "RX_RX") (pintype "bidirectional"))
    )
    (net (code "72") (name "USART5_RX") (class "Default")
      (node (ref "U$1") (pin "D2") (pinfunction "D2,USART5_RX,SDIO_CMD_D2") (pintype "bidirectional"))
      (node (ref "U$17") (pin "TX") (pinfunction "TX_5V_TX") (pintype "bidirectional"))
    )
    (net (code "73") (name "unconnected-(MPU-9250-AUX_CL-Pad7)") (class "Default")
      (node (ref "MPU-9250") (pin "7") (pinfunction "AUX_CL_7") (pintype "bidirectional"))
    )
    (net (code "74") (name "unconnected-(MPU-9250-AUX_DA-Pad8)") (class "Default")
      (node (ref "MPU-9250") (pin "8") (pinfunction "AUX_DA_8") (pintype "bidirectional"))
    )
    (net (code "75") (name "unconnected-(MPU-9250-INT-Pad9)") (class "Default")
      (node (ref "MPU-9250") (pin "9") (pinfunction "INT_9") (pintype "bidirectional"))
    )
    (net (code "76") (name "unconnected-(U$1-B0,TIM3_CH3{slash}ADC12_8-PadB0)") (class "Default")
      (node (ref "U$1") (pin "B0") (pinfunction "B0,TIM3_CH3/ADC12_8_B0") (pintype "bidirectional"))
    )
    (net (code "77") (name "unconnected-(U$1-PadRES)") (class "Default")
      (node (ref "U$1") (pin "RES") (pinfunction "RES_RES") (pintype "bidirectional"))
    )
    (net (code "78") (name "unconnected-(U$19-PadTX)") (class "Default")
      (node (ref "U$19") (pin "TX") (pinfunction "TX_TX") (pintype "bidirectional"))
    )
  )
)
